# 1-Schematic_first_pcb.net
KiCad netlist of a schematic drawn in EasyEDA
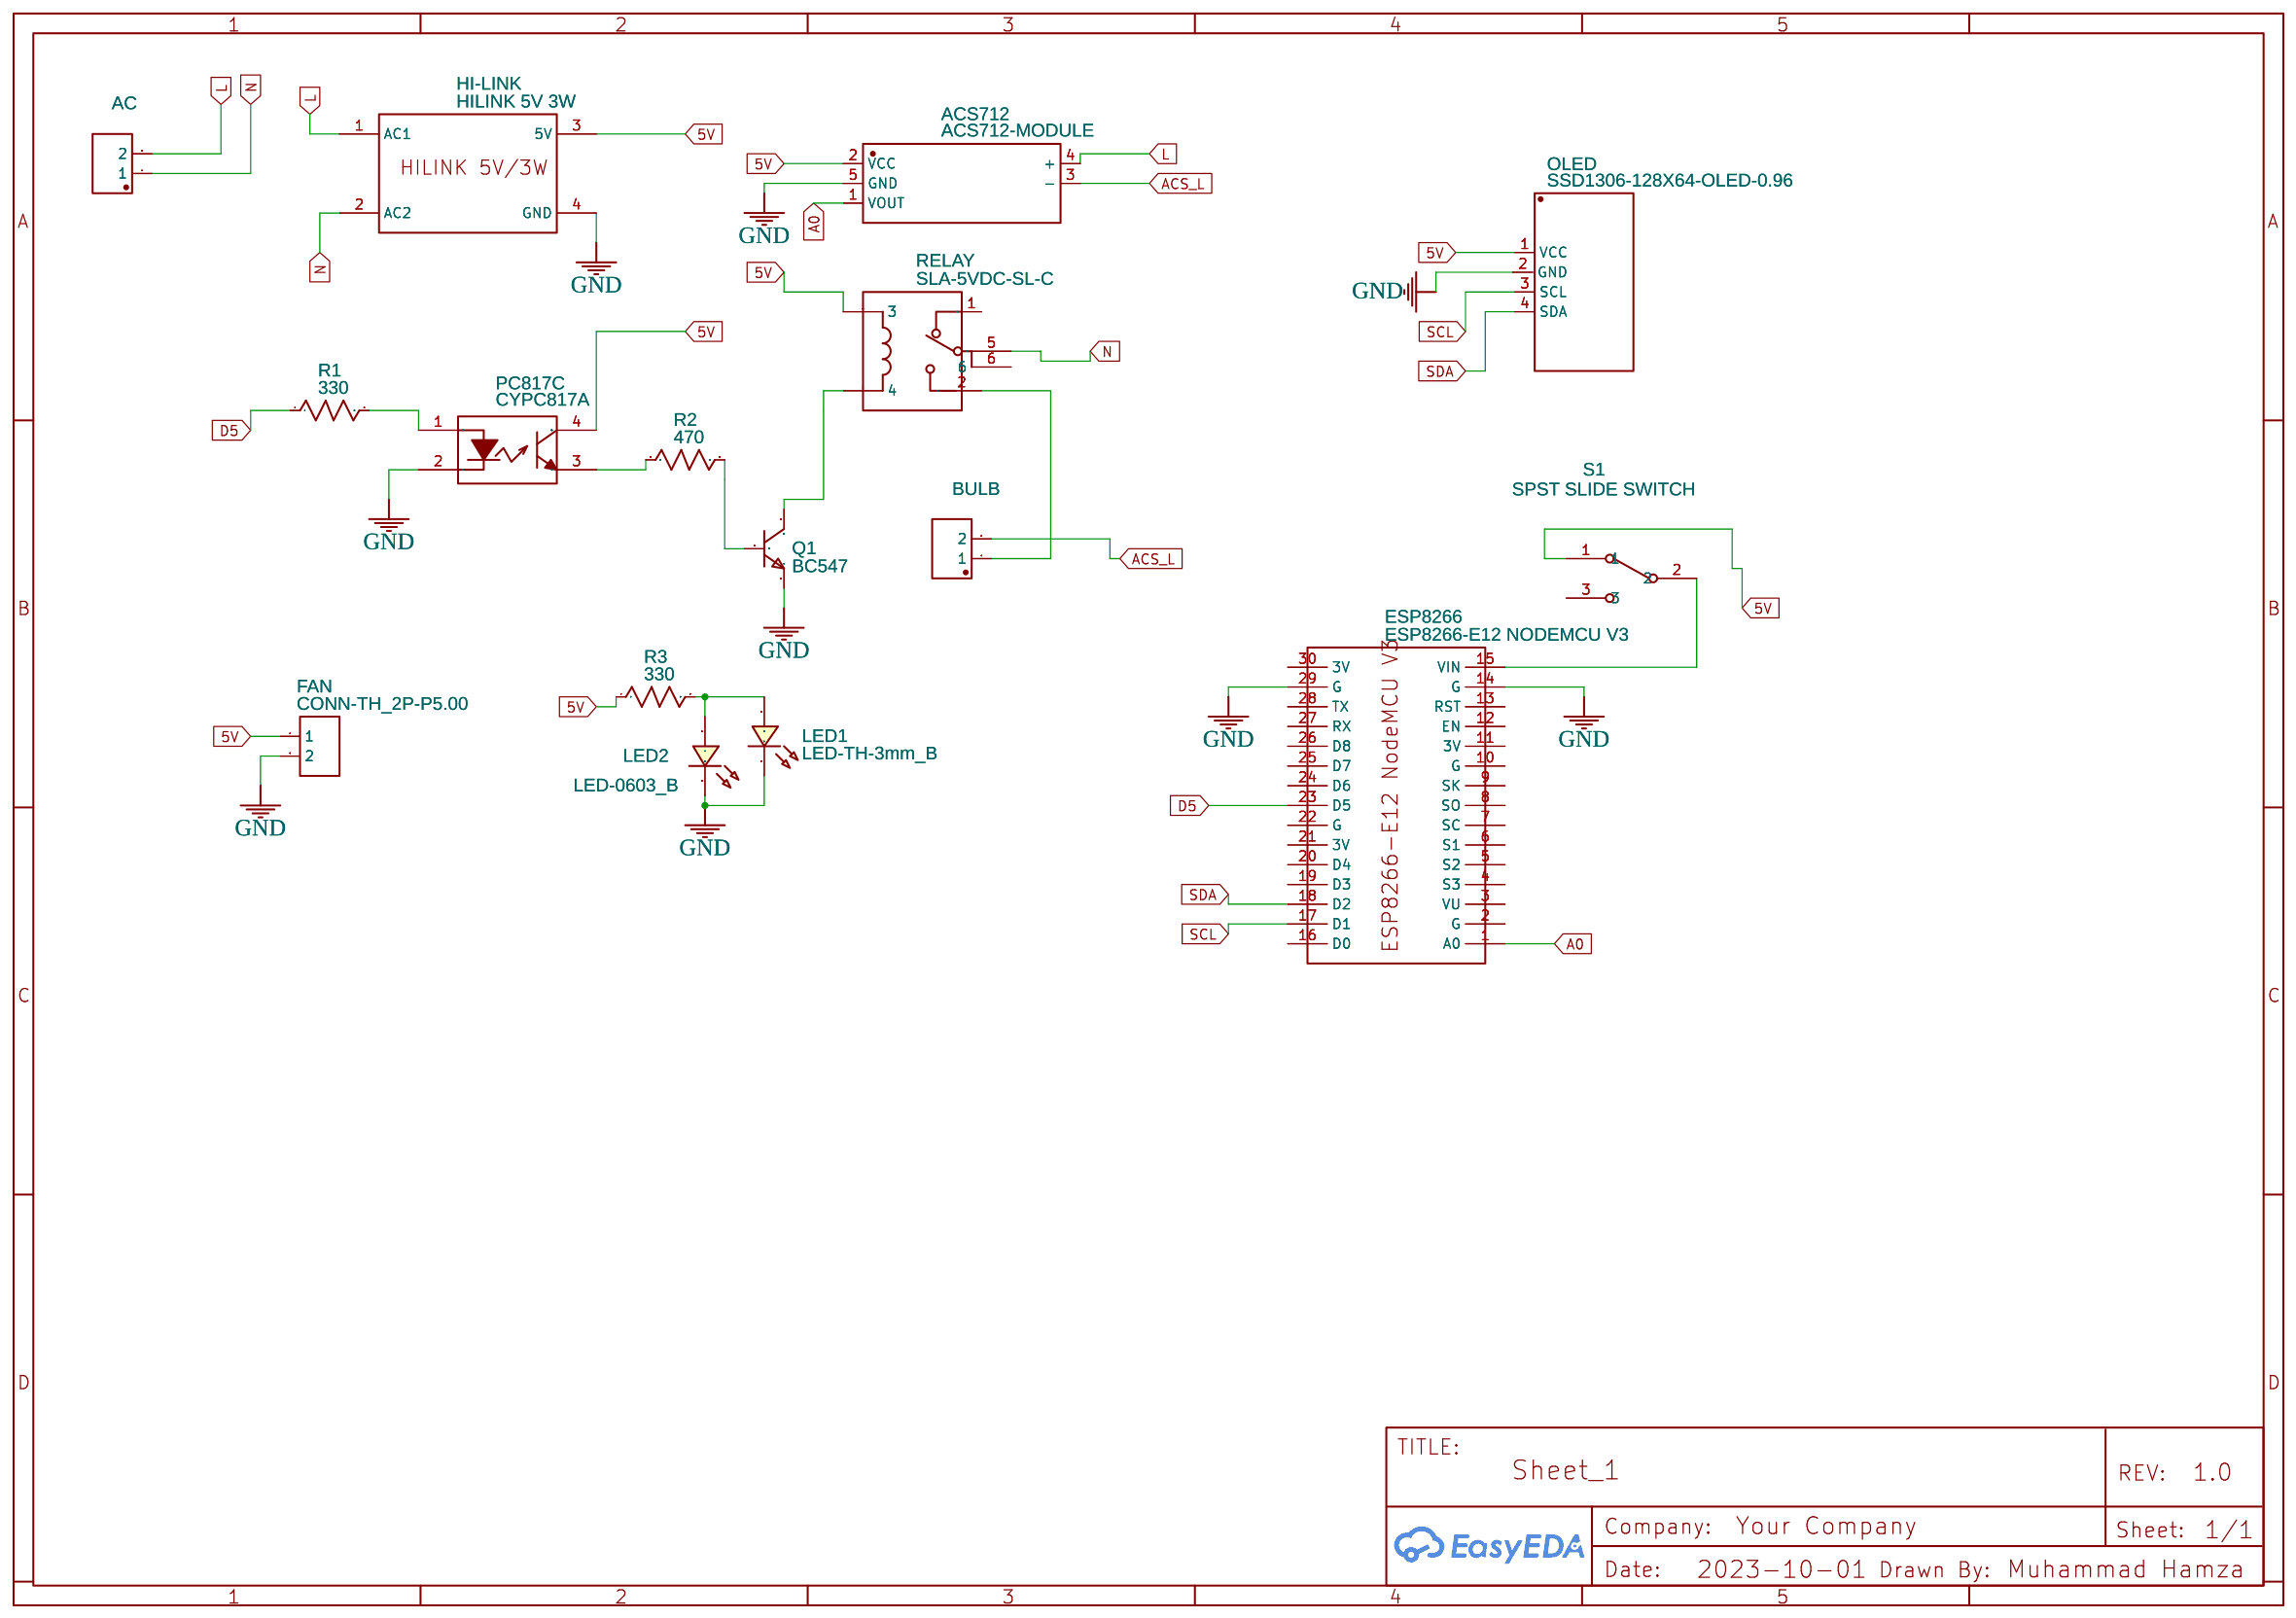
[diagram p0: schematic sheet]

(export (version "E")
  (design (tool "Eeschema 10.0.6"))
  (components
    (comp (ref "AC")
      (value "NO")
      (fields (field (name "Manufacturer Part") "n/a"))
      (libsource (lib "") (part "Terminal_Block_9.5mm_2P"))
    )
    (comp (ref "ACS712")
      (value "ACS712-MODULE")
      (fields (field (name "Manufacturer Part") "DIY PCB S09"))
      (libsource (lib "") (part "ACS712-MODULE"))
    )
    (comp (ref "BULB")
      (value "NO")
      (fields (field (name "Manufacturer Part") "n/a"))
      (libsource (lib "") (part "Terminal_Block_9.5mm_2P_1"))
    )
    (comp (ref "ESP8266")
      (value "ESP8266-E12 NODEMCU V3")
      (libsource (lib "") (part "ESP8266-E12 NODEMCU V3"))
    )
    (comp (ref "FAN") (value "CONN-TH_2P-P5.00") (libsource (lib "") (part "CONN-TH_2P-P5.00")))
    (comp (ref "HI-LINK")
      (value "HILINK 5V 3W")
      (fields (field (name "Manufacturer Part") "HILINK 5V"))
      (libsource (lib "") (part "HILINK 5V 3W"))
    )
    (comp (ref "LED1")
      (value "LED-TH-3mm_B")
      (fields
        (field (name "Manufacturer Part") "204-10SUBC/S400-A4")
        (field (name "Manufacturer") "EVERLIGHT(台湾亿光)")
      )
      (libsource (lib "") (part "LED-TH-3mm_B"))
    )
    (comp (ref "LED2")
      (value "LED-0603_B")
      (fields
        (field (name "Manufacturer Part") "19-217/BHC-ZL1M2RY/3T")
        (field (name "Manufacturer") "EVERLIGHT(台湾亿光)")
      )
      (libsource (lib "") (part "LED-0603_B"))
    )
    (comp (ref "OLED")
      (value "SSD1306-128X64-OLED-0.96")
      (libsource (lib "") (part "SSD1306-128X64-OLED-0.96"))
    )
    (comp (ref "PC817C")
      (value "CYPC817A")
      (fields (field (name "Manufacturer") "OCIC(卓睿科)"))
      (libsource (lib "") (part "CYPC817A"))
    )
    (comp (ref "Q1")
      (value "BC547")
      (fields (field (name "Manufacturer Part") "BC547BTA") (field (name "Manufacturer") "ON Semicon"))
      (libsource (lib "") (part "BC547"))
    )
    (comp (ref "R1") (value "330") (libsource (lib "") (part "R_AXIAL-0.4_US")))
    (comp (ref "R2") (value "470") (libsource (lib "") (part "R_AXIAL-0.4_US")))
    (comp (ref "R3") (value "330") (libsource (lib "") (part "R_AXIAL-0.4_US")))
    (comp (ref "RELAY")
      (value "SLA-5VDC-SL-C")
      (fields (field (name "Manufacturer") "松乐"))
      (libsource (lib "") (part "SLA-5VDC-SL-C"))
    )
    (comp (ref "S1") (value "SPST SLIDE SWITCH") (libsource (lib "") (part "SPST SLIDE SWITCH")))
  )
  (nets
    (net (code "1") (name "5V") (class "Default")
      (node (ref "ACS712") (pin "2") (pinfunction "VCC_2") (pintype "unspecified"))
      (node (ref "FAN") (pin "1") (pinfunction "1_1") (pintype "unspecified"))
      (node (ref "HI-LINK") (pin "3") (pinfunction "5V_3") (pintype "unspecified"))
      (node (ref "OLED") (pin "1") (pinfunction "VCC_1") (pintype "passive"))
      (node (ref "PC817C") (pin "4") (pinfunction "COL_4") (pintype "unspecified"))
      (node (ref "R3") (pin "1") (pinfunction "1_1") (pintype "unspecified"))
      (node (ref "RELAY") (pin "3") (pinfunction "3_3") (pintype "unspecified"))
      (node (ref "S1") (pin "1") (pinfunction "1_1") (pintype "unspecified"))
    )
    (net (code "2") (name "A0") (class "Default")
      (node (ref "ACS712") (pin "1") (pinfunction "VOUT_1") (pintype "unspecified"))
      (node (ref "ESP8266") (pin "1") (pinfunction "A0_1") (pintype "unspecified"))
    )
    (net (code "3") (name "ACS_L") (class "Default")
      (node (ref "ACS712") (pin "3") (pinfunction "-_3") (pintype "unspecified"))
      (node (ref "BULB") (pin "2") (pinfunction "2_2") (pintype "unspecified"))
    )
    (net (code "4") (name "D5") (class "Default")
      (node (ref "ESP8266") (pin "23") (pinfunction "D5_23") (pintype "unspecified"))
      (node (ref "R1") (pin "1") (pinfunction "1_1") (pintype "unspecified"))
    )
    (net (code "5") (name "GND") (class "Default")
      (node (ref "ACS712") (pin "5") (pinfunction "GND_5") (pintype "unspecified"))
      (node (ref "ESP8266") (pin "14") (pinfunction "G_14") (pintype "unspecified"))
      (node (ref "ESP8266") (pin "29") (pinfunction "G_29") (pintype "unspecified"))
      (node (ref "FAN") (pin "2") (pinfunction "2_2") (pintype "unspecified"))
      (node (ref "HI-LINK") (pin "4") (pinfunction "GND_4") (pintype "unspecified"))
      (node (ref "LED1") (pin "2") (pinfunction "2_2") (pintype "unspecified"))
      (node (ref "LED2") (pin "2") (pinfunction "2_2") (pintype "unspecified"))
      (node (ref "OLED") (pin "2") (pinfunction "GND_2") (pintype "passive"))
      (node (ref "PC817C") (pin "2") (pinfunction "CAT_2") (pintype "unspecified"))
      (node (ref "Q1") (pin "3") (pinfunction "E_3") (pintype "unspecified"))
    )
    (net (code "6") (name "L") (class "Default")
      (node (ref "AC") (pin "2") (pinfunction "2_2") (pintype "unspecified"))
      (node (ref "ACS712") (pin "4") (pinfunction "+_4") (pintype "unspecified"))
      (node (ref "HI-LINK") (pin "1") (pinfunction "AC1_1") (pintype "unspecified"))
    )
    (net (code "7") (name "N") (class "Default")
      (node (ref "AC") (pin "1") (pinfunction "1_1") (pintype "unspecified"))
      (node (ref "HI-LINK") (pin "2") (pinfunction "AC2_2") (pintype "unspecified"))
      (node (ref "RELAY") (pin "5") (pinfunction "5_5") (pintype "unspecified"))
    )
    (net (code "8") (name "Net-(BULB-Pad1)") (class "Default")
      (node (ref "BULB") (pin "1") (pinfunction "1_1") (pintype "unspecified"))
      (node (ref "RELAY") (pin "2") (pinfunction "2_2") (pintype "unspecified"))
    )
    (net (code "9") (name "Net-(ESP8266-VIN)") (class "Default")
      (node (ref "ESP8266") (pin "15") (pinfunction "VIN_15") (pintype "unspecified"))
      (node (ref "S1") (pin "2") (pinfunction "2_2") (pintype "unspecified"))
    )
    (net (code "10") (name "Net-(LED1-Pad1)") (class "Default")
      (node (ref "LED1") (pin "1") (pinfunction "1_1") (pintype "unspecified"))
      (node (ref "LED2") (pin "1") (pinfunction "1_1") (pintype "unspecified"))
      (node (ref "R3") (pin "2") (pinfunction "2_2") (pintype "unspecified"))
    )
    (net (code "11") (name "Net-(PC817C-AN)") (class "Default")
      (node (ref "PC817C") (pin "1") (pinfunction "AN_1") (pintype "unspecified"))
      (node (ref "R1") (pin "2") (pinfunction "2_2") (pintype "unspecified"))
    )
    (net (code "12") (name "Net-(PC817C-EM)") (class "Default")
      (node (ref "PC817C") (pin "3") (pinfunction "EM_3") (pintype "unspecified"))
      (node (ref "R2") (pin "1") (pinfunction "1_1") (pintype "unspecified"))
    )
    (net (code "13") (name "Net-(Q1-B)") (class "Default")
      (node (ref "Q1") (pin "2") (pinfunction "B_2") (pintype "unspecified"))
      (node (ref "R2") (pin "2") (pinfunction "2_2") (pintype "unspecified"))
    )
    (net (code "14") (name "Net-(Q1-C)") (class "Default")
      (node (ref "Q1") (pin "1") (pinfunction "C_1") (pintype "unspecified"))
      (node (ref "RELAY") (pin "4") (pinfunction "4_4") (pintype "unspecified"))
    )
    (net (code "15") (name "SCL") (class "Default")
      (node (ref "ESP8266") (pin "17") (pinfunction "D1_17") (pintype "unspecified"))
      (node (ref "OLED") (pin "3") (pinfunction "SCL_3") (pintype "input"))
    )
    (net (code "16") (name "SDA") (class "Default")
      (node (ref "ESP8266") (pin "18") (pinfunction "D2_18") (pintype "unspecified"))
      (node (ref "OLED") (pin "4") (pinfunction "SDA_4") (pintype "input"))
    )
    (net (code "17") (name "unconnected-(ESP8266-3V-Pad11)") (class "Default")
      (node (ref "ESP8266") (pin "11") (pinfunction "3V_11") (pintype "unspecified"))
    )
    (net (code "18") (name "unconnected-(ESP8266-3V-Pad21)") (class "Default")
      (node (ref "ESP8266") (pin "21") (pinfunction "3V_21") (pintype "unspecified"))
    )
    (net (code "19") (name "unconnected-(ESP8266-3V-Pad30)") (class "Default")
      (node (ref "ESP8266") (pin "30") (pinfunction "3V_30") (pintype "unspecified"))
    )
    (net (code "20") (name "unconnected-(ESP8266-D0-Pad16)") (class "Default")
      (node (ref "ESP8266") (pin "16") (pinfunction "D0_16") (pintype "unspecified"))
    )
    (net (code "21") (name "unconnected-(ESP8266-D3-Pad19)") (class "Default")
      (node (ref "ESP8266") (pin "19") (pinfunction "D3_19") (pintype "unspecified"))
    )
    (net (code "22") (name "unconnected-(ESP8266-D4-Pad20)") (class "Default")
      (node (ref "ESP8266") (pin "20") (pinfunction "D4_20") (pintype "unspecified"))
    )
    (net (code "23") (name "unconnected-(ESP8266-D6-Pad24)") (class "Default")
      (node (ref "ESP8266") (pin "24") (pinfunction "D6_24") (pintype "unspecified"))
    )
    (net (code "24") (name "unconnected-(ESP8266-D7-Pad25)") (class "Default")
      (node (ref "ESP8266") (pin "25") (pinfunction "D7_25") (pintype "unspecified"))
    )
    (net (code "25") (name "unconnected-(ESP8266-D8-Pad26)") (class "Default")
      (node (ref "ESP8266") (pin "26") (pinfunction "D8_26") (pintype "unspecified"))
    )
    (net (code "26") (name "unconnected-(ESP8266-EN-Pad12)") (class "Default")
      (node (ref "ESP8266") (pin "12") (pinfunction "EN_12") (pintype "unspecified"))
    )
    (net (code "27") (name "unconnected-(ESP8266-G-Pad2)") (class "Default")
      (node (ref "ESP8266") (pin "2") (pinfunction "G_2") (pintype "unspecified"))
    )
    (net (code "28") (name "unconnected-(ESP8266-G-Pad10)") (class "Default")
      (node (ref "ESP8266") (pin "10") (pinfunction "G_10") (pintype "unspecified"))
    )
    (net (code "29") (name "unconnected-(ESP8266-G-Pad22)") (class "Default")
      (node (ref "ESP8266") (pin "22") (pinfunction "G_22") (pintype "unspecified"))
    )
    (net (code "30") (name "unconnected-(ESP8266-RST-Pad13)") (class "Default")
      (node (ref "ESP8266") (pin "13") (pinfunction "RST_13") (pintype "unspecified"))
    )
    (net (code "31") (name "unconnected-(ESP8266-RX-Pad27)") (class "Default")
      (node (ref "ESP8266") (pin "27") (pinfunction "RX_27") (pintype "unspecified"))
    )
    (net (code "32") (name "unconnected-(ESP8266-S1-Pad6)") (class "Default")
      (node (ref "ESP8266") (pin "6") (pinfunction "S1_6") (pintype "unspecified"))
    )
    (net (code "33") (name "unconnected-(ESP8266-S2-Pad5)") (class "Default")
      (node (ref "ESP8266") (pin "5") (pinfunction "S2_5") (pintype "unspecified"))
    )
    (net (code "34") (name "unconnected-(ESP8266-S3-Pad4)") (class "Default")
      (node (ref "ESP8266") (pin "4") (pinfunction "S3_4") (pintype "unspecified"))
    )
    (net (code "35") (name "unconnected-(ESP8266-SC-Pad7)") (class "Default")
      (node (ref "ESP8266") (pin "7") (pinfunction "SC_7") (pintype "unspecified"))
    )
    (net (code "36") (name "unconnected-(ESP8266-SK-Pad9)") (class "Default")
      (node (ref "ESP8266") (pin "9") (pinfunction "SK_9") (pintype "unspecified"))
    )
    (net (code "37") (name "unconnected-(ESP8266-SO-Pad8)") (class "Default")
      (node (ref "ESP8266") (pin "8") (pinfunction "SO_8") (pintype "unspecified"))
    )
    (net (code "38") (name "unconnected-(ESP8266-TX-Pad28)") (class "Default")
      (node (ref "ESP8266") (pin "28") (pinfunction "TX_28") (pintype "unspecified"))
    )
    (net (code "39") (name "unconnected-(ESP8266-VU-Pad3)") (class "Default")
      (node (ref "ESP8266") (pin "3") (pinfunction "VU_3") (pintype "unspecified"))
    )
    (net (code "40") (name "unconnected-(RELAY-Pad1)") (class "Default")
      (node (ref "RELAY") (pin "1") (pinfunction "1_1") (pintype "unspecified"))
    )
    (net (code "41") (name "unconnected-(RELAY-Pad6)") (class "Default")
      (node (ref "RELAY") (pin "6") (pinfunction "6_6") (pintype "unspecified"))
    )
    (net (code "42") (name "unconnected-(S1-Pad3)") (class "Default")
      (node (ref "S1") (pin "3") (pinfunction "3_3") (pintype "unspecified"))
    )
  )
)
